# OneShot_Relais_Timer_UI.net
KiCad netlist of a schematic drawn in EAGLE
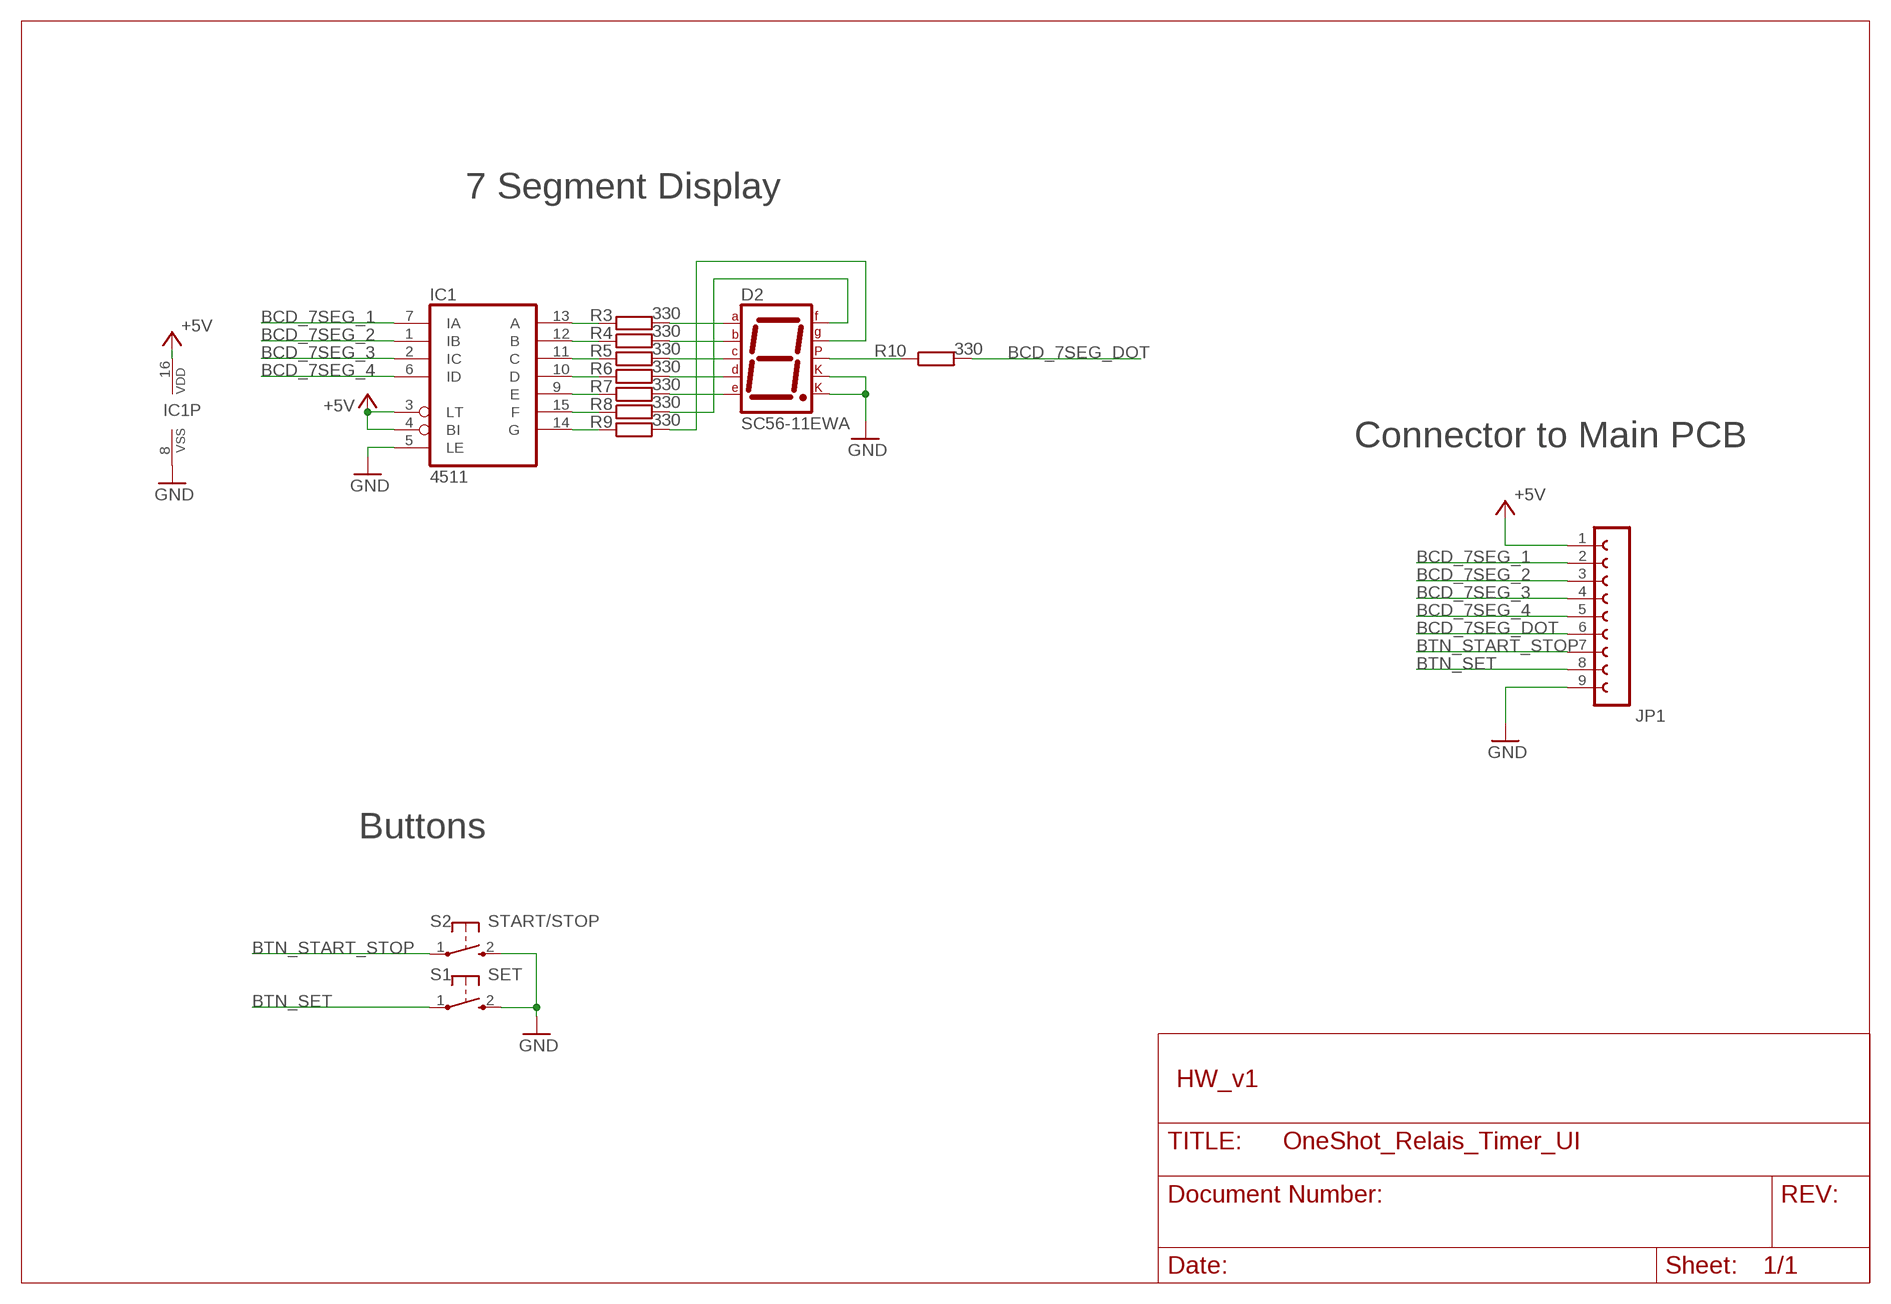
[diagram p0: schematic, sheet 1]

(export (version "E")
  (design (tool "Eeschema 10.0.6"))
  (components
    (comp (ref "D2")
      (value "SC56-11EWA")
      (footprint "eagle-import:7SEG-13")
      (libsource (lib "eagle-import") (part "7SEG-CK"))
    )
    (comp (ref "IC1")
      (value "4511")
      (footprint "eagle-import:SOIC127P1032X265-16L")
      (libsource (lib "eagle-import") (part "4511"))
    )
    (comp (ref "JP1")
      (value "FE09-1")
      (footprint "eagle-import:FE09")
      (libsource (lib "eagle-import") (part "FE09-1"))
    )
    (comp (ref "R3")
      (value "330")
      (footprint "eagle-import:R0805")
      (libsource (lib "eagle-import") (part "R-EU_R0805"))
    )
    (comp (ref "R4")
      (value "330")
      (footprint "eagle-import:R0805")
      (libsource (lib "eagle-import") (part "R-EU_R0805"))
    )
    (comp (ref "R5")
      (value "330")
      (footprint "eagle-import:R0805")
      (libsource (lib "eagle-import") (part "R-EU_R0805"))
    )
    (comp (ref "R6")
      (value "330")
      (footprint "eagle-import:R0805")
      (libsource (lib "eagle-import") (part "R-EU_R0805"))
    )
    (comp (ref "R7")
      (value "330")
      (footprint "eagle-import:R0805")
      (libsource (lib "eagle-import") (part "R-EU_R0805"))
    )
    (comp (ref "R8")
      (value "330")
      (footprint "eagle-import:R0805")
      (libsource (lib "eagle-import") (part "R-EU_R0805"))
    )
    (comp (ref "R9")
      (value "330")
      (footprint "eagle-import:R0805")
      (libsource (lib "eagle-import") (part "R-EU_R0805"))
    )
    (comp (ref "R10")
      (value "330")
      (footprint "eagle-import:R0805")
      (libsource (lib "eagle-import") (part "R-EU_R0805"))
    )
    (comp (ref "S1")
      (value "SET")
      (footprint "eagle-import:B3F-10XX")
      (libsource (lib "eagle-import") (part "KURZHUBTASTER"))
    )
    (comp (ref "S2")
      (value "START/STOP")
      (footprint "eagle-import:B3F-10XX")
      (libsource (lib "eagle-import") (part "KURZHUBTASTER"))
    )
  )
  (nets
    (net (code "1") (name "+5V") (class "Default")
      (node (ref "IC1") (pin "16") (pinfunction "VDD_16") (pintype "power_in"))
      (node (ref "IC1") (pin "3") (pinfunction "LT_3") (pintype "input"))
      (node (ref "IC1") (pin "4") (pinfunction "BI_4") (pintype "input"))
      (node (ref "JP1") (pin "1") (pinfunction "1_1") (pintype "passive"))
    )
    (net (code "2") (name "/BCD_7SEG_1") (class "Default")
      (node (ref "IC1") (pin "7") (pinfunction "IA_7") (pintype "input"))
      (node (ref "JP1") (pin "2") (pinfunction "2_2") (pintype "passive"))
    )
    (net (code "3") (name "/BCD_7SEG_2") (class "Default")
      (node (ref "IC1") (pin "1") (pinfunction "IB_1") (pintype "input"))
      (node (ref "JP1") (pin "3") (pinfunction "3_3") (pintype "passive"))
    )
    (net (code "4") (name "/BCD_7SEG_3") (class "Default")
      (node (ref "IC1") (pin "2") (pinfunction "IC_2") (pintype "input"))
      (node (ref "JP1") (pin "4") (pinfunction "4_4") (pintype "passive"))
    )
    (net (code "5") (name "/BCD_7SEG_4") (class "Default")
      (node (ref "IC1") (pin "6") (pinfunction "ID_6") (pintype "input"))
      (node (ref "JP1") (pin "5") (pinfunction "5_5") (pintype "passive"))
    )
    (net (code "6") (name "/BCD_7SEG_DOT") (class "Default")
      (node (ref "JP1") (pin "6") (pinfunction "6_6") (pintype "passive"))
      (node (ref "R10") (pin "2") (pinfunction "2_2") (pintype "passive"))
    )
    (net (code "7") (name "/BTN_SET") (class "Default")
      (node (ref "JP1") (pin "8") (pinfunction "8_8") (pintype "passive"))
      (node (ref "S1") (pin "1") (pinfunction "P_1") (pintype "passive"))
    )
    (net (code "8") (name "/BTN_START_STOP") (class "Default")
      (node (ref "JP1") (pin "7") (pinfunction "7_7") (pintype "passive"))
      (node (ref "S2") (pin "1") (pinfunction "P_1") (pintype "passive"))
    )
    (net (code "9") (name "GND") (class "Default")
      (node (ref "D2") (pin "3") (pinfunction "CK1_3") (pintype "passive"))
      (node (ref "D2") (pin "8") (pinfunction "CK2_8") (pintype "passive"))
      (node (ref "IC1") (pin "5") (pinfunction "LE_5") (pintype "input"))
      (node (ref "IC1") (pin "8") (pinfunction "VSS_8") (pintype "power_in"))
      (node (ref "JP1") (pin "9") (pinfunction "9_9") (pintype "passive"))
      (node (ref "S1") (pin "2") (pinfunction "S_2") (pintype "passive"))
      (node (ref "S2") (pin "2") (pinfunction "S_2") (pintype "passive"))
    )
    (net (code "10") (name "Net-(D2-A)") (class "Default")
      (node (ref "D2") (pin "7") (pinfunction "A_7") (pintype "passive"))
      (node (ref "R3") (pin "2") (pinfunction "2_2") (pintype "passive"))
    )
    (net (code "11") (name "Net-(D2-B)") (class "Default")
      (node (ref "D2") (pin "6") (pinfunction "B_6") (pintype "passive"))
      (node (ref "R4") (pin "2") (pinfunction "2_2") (pintype "passive"))
    )
    (net (code "12") (name "Net-(D2-C)") (class "Default")
      (node (ref "D2") (pin "4") (pinfunction "C_4") (pintype "passive"))
      (node (ref "R5") (pin "2") (pinfunction "2_2") (pintype "passive"))
    )
    (net (code "13") (name "Net-(D2-D)") (class "Default")
      (node (ref "D2") (pin "2") (pinfunction "D_2") (pintype "passive"))
      (node (ref "R6") (pin "2") (pinfunction "2_2") (pintype "passive"))
    )
    (net (code "14") (name "Net-(D2-DP)") (class "Default")
      (node (ref "D2") (pin "5") (pinfunction "DP_5") (pintype "passive"))
      (node (ref "R10") (pin "1") (pinfunction "1_1") (pintype "passive"))
    )
    (net (code "15") (name "Net-(D2-E)") (class "Default")
      (node (ref "D2") (pin "1") (pinfunction "E_1") (pintype "passive"))
      (node (ref "R7") (pin "2") (pinfunction "2_2") (pintype "passive"))
    )
    (net (code "16") (name "Net-(D2-F)") (class "Default")
      (node (ref "D2") (pin "9") (pinfunction "F_9") (pintype "passive"))
      (node (ref "R8") (pin "2") (pinfunction "2_2") (pintype "passive"))
    )
    (net (code "17") (name "Net-(D2-G)") (class "Default")
      (node (ref "D2") (pin "10") (pinfunction "G_10") (pintype "passive"))
      (node (ref "R9") (pin "2") (pinfunction "2_2") (pintype "passive"))
    )
    (net (code "18") (name "Net-(IC1A-A)") (class "Default")
      (node (ref "IC1") (pin "13") (pinfunction "A_13") (pintype "output"))
      (node (ref "R3") (pin "1") (pinfunction "1_1") (pintype "passive"))
    )
    (net (code "19") (name "Net-(IC1A-B)") (class "Default")
      (node (ref "IC1") (pin "12") (pinfunction "B_12") (pintype "output"))
      (node (ref "R4") (pin "1") (pinfunction "1_1") (pintype "passive"))
    )
    (net (code "20") (name "Net-(IC1A-C)") (class "Default")
      (node (ref "IC1") (pin "11") (pinfunction "C_11") (pintype "output"))
      (node (ref "R5") (pin "1") (pinfunction "1_1") (pintype "passive"))
    )
    (net (code "21") (name "Net-(IC1A-D)") (class "Default")
      (node (ref "IC1") (pin "10") (pinfunction "D_10") (pintype "output"))
      (node (ref "R6") (pin "1") (pinfunction "1_1") (pintype "passive"))
    )
    (net (code "22") (name "Net-(IC1A-E)") (class "Default")
      (node (ref "IC1") (pin "9") (pinfunction "E_9") (pintype "output"))
      (node (ref "R7") (pin "1") (pinfunction "1_1") (pintype "passive"))
    )
    (net (code "23") (name "Net-(IC1A-F)") (class "Default")
      (node (ref "IC1") (pin "15") (pinfunction "F_15") (pintype "output"))
      (node (ref "R8") (pin "1") (pinfunction "1_1") (pintype "passive"))
    )
    (net (code "24") (name "Net-(IC1A-G)") (class "Default")
      (node (ref "IC1") (pin "14") (pinfunction "G_14") (pintype "output"))
      (node (ref "R9") (pin "1") (pinfunction "1_1") (pintype "passive"))
    )
  )
)
